# Ethernet.net
KiCad netlist of a schematic drawn in Altium Designer
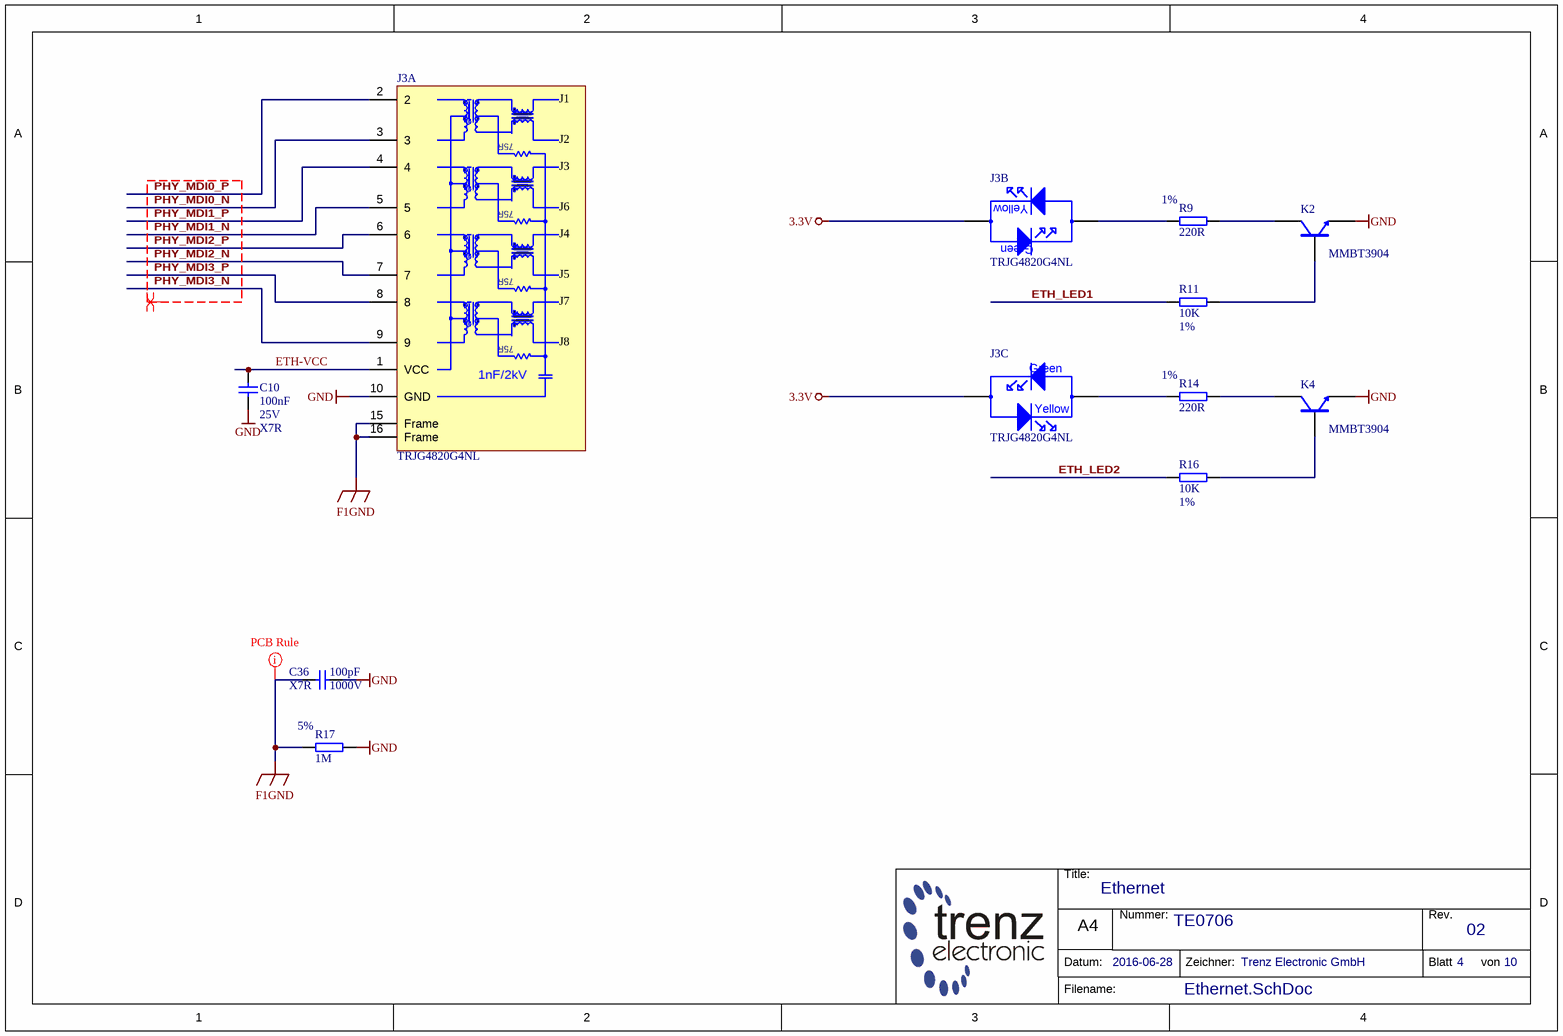
[diagram p0: Ethernet.SchDoc]

(export (version "E")
  (design (tool "Eeschema 10.0.6"))
  (components
    (comp (ref "C10")
      (value "100nF")
      (footprint "CAPC1005X55N")
      (description "KON 100nF 25V X5R SMD")
      (fields (field (name "VOLTAGE") "25V") (field (name "TECHNOLOGY") "X7R"))
      (libsource (lib "TE") (part "CAP-NP"))
    )
    (comp (ref "C36")
      (value "100pF")
      (footprint "CAPC3216X180N")
      (description "KON 100pF 1000V X7R 10%")
      (fields
        (field (name "VOLTAGE") "X7R")
        (field (name "TECHNOLOGY") "1000V")
        (field (name "TOLERANCE") "10%")
      )
      (libsource (lib "TE") (part "CAP-NP"))
    )
    (comp (ref "J3")
      (value "TRJG4820G4NL")
      (footprint "MIC38013-5151T-LF3")
      (description "LAN-Transformer 10/100/1000 BaseT")
      (libsource (lib "TE") (part "WE-RJ45LAN"))
    )
    (comp (ref "K2")
      (value "MMBT3904")
      (footprint "SOT95P280X145-3N")
      (libsource (lib "TE") (part "NPN-SOT23"))
    )
    (comp (ref "K4")
      (value "MMBT3904")
      (footprint "SOT95P280X145-3N")
      (libsource (lib "TE") (part "NPN-SOT23"))
    )
    (comp (ref "R9")
      (value "220R")
      (footprint "RESC1005X40N")
      (description "WID SMD 220R 1% 0,063W")
      (fields (field (name "TOLERANCE") "1%"))
      (libsource (lib "TE") (part "RES"))
    )
    (comp (ref "R11")
      (value "10K")
      (footprint "RESC1005X40N")
      (description "WID SMD 10K 1% 0,063W")
      (fields (field (name "TOLERANCE") "1%"))
      (libsource (lib "TE") (part "RES"))
    )
    (comp (ref "R14")
      (value "220R")
      (footprint "RESC1005X40N")
      (description "WID SMD 220R 1% 0,063W")
      (fields (field (name "TOLERANCE") "1%"))
      (libsource (lib "TE") (part "RES"))
    )
    (comp (ref "R16")
      (value "10K")
      (footprint "RESC1005X40N")
      (description "WID SMD 10K 1% 0,063W")
      (fields (field (name "TOLERANCE") "1%"))
      (libsource (lib "TE") (part "RES"))
    )
    (comp (ref "R17")
      (value "1M")
      (footprint "RESC3216X65N")
      (description "WID SMD 1M 5% 0,25W")
      (fields (field (name "TOLERANCE") "5%"))
      (libsource (lib "TE") (part "RES"))
    )
  )
  (nets
    (net (code "1") (name "/ETH-VCC") (class "Default")
      (node (ref "C10") (pin "2") (pinfunction "2_2") (pintype "passive"))
      (node (ref "J3") (pin "1") (pinfunction "VCC_1") (pintype "power_in"))
    )
    (net (code "2") (name "/ETH_LED1") (class "Default")
      (node (ref "R11") (pin "1") (pinfunction "1_1") (pintype "passive"))
    )
    (net (code "3") (name "/ETH_LED2") (class "Default")
      (node (ref "R16") (pin "1") (pinfunction "1_1") (pintype "passive"))
    )
    (net (code "4") (name "/PHY_MDI0_N") (class "Default")
      (node (ref "J3") (pin "3") (pinfunction "3_3") (pintype "passive"))
    )
    (net (code "5") (name "/PHY_MDI0_P") (class "Default")
      (node (ref "J3") (pin "2") (pinfunction "2_2") (pintype "passive"))
    )
    (net (code "6") (name "/PHY_MDI1_N") (class "Default")
      (node (ref "J3") (pin "5") (pinfunction "5_5") (pintype "passive"))
    )
    (net (code "7") (name "/PHY_MDI1_P") (class "Default")
      (node (ref "J3") (pin "4") (pinfunction "4_4") (pintype "passive"))
    )
    (net (code "8") (name "/PHY_MDI2_N") (class "Default")
      (node (ref "J3") (pin "7") (pinfunction "7_7") (pintype "passive"))
    )
    (net (code "9") (name "/PHY_MDI2_P") (class "Default")
      (node (ref "J3") (pin "6") (pinfunction "6_6") (pintype "passive"))
    )
    (net (code "10") (name "/PHY_MDI3_N") (class "Default")
      (node (ref "J3") (pin "9") (pinfunction "9_9") (pintype "passive"))
    )
    (net (code "11") (name "/PHY_MDI3_P") (class "Default")
      (node (ref "J3") (pin "8") (pinfunction "8_8") (pintype "passive"))
    )
    (net (code "12") (name "3.3V") (class "Default")
      (node (ref "J3") (pin "11") (pinfunction "GREEN_11") (pintype "passive"))
      (node (ref "J3") (pin "14") (pinfunction "YELLOW_14") (pintype "passive"))
    )
    (net (code "13") (name "F1GND") (class "Default")
      (node (ref "C36") (pin "1") (pinfunction "1_1") (pintype "passive"))
      (node (ref "J3") (pin "15") (pinfunction "Frame_15") (pintype "passive"))
      (node (ref "J3") (pin "16") (pinfunction "Frame_16") (pintype "passive"))
      (node (ref "R17") (pin "1") (pinfunction "1_1") (pintype "passive"))
    )
    (net (code "14") (name "GND") (class "Default")
      (node (ref "C10") (pin "1") (pinfunction "1_1") (pintype "passive"))
      (node (ref "C36") (pin "2") (pinfunction "2_2") (pintype "passive"))
      (node (ref "J3") (pin "10") (pinfunction "GND_10") (pintype "power_in"))
      (node (ref "K2") (pin "2") (pinfunction "EMITTER_2") (pintype "passive"))
      (node (ref "K4") (pin "2") (pinfunction "EMITTER_2") (pintype "passive"))
      (node (ref "R17") (pin "2") (pinfunction "2_2") (pintype "passive"))
    )
    (net (code "15") (name "Net-(J3B-YELLOW)") (class "Default")
      (node (ref "J3") (pin "12") (pinfunction "YELLOW_12") (pintype "passive"))
      (node (ref "R9") (pin "1") (pinfunction "1_1") (pintype "passive"))
    )
    (net (code "16") (name "Net-(J3C-GREEN)") (class "Default")
      (node (ref "J3") (pin "13") (pinfunction "GREEN_13") (pintype "passive"))
      (node (ref "R14") (pin "1") (pinfunction "1_1") (pintype "passive"))
    )
    (net (code "17") (name "Net-(K2-BASIS)") (class "Default")
      (node (ref "K2") (pin "1") (pinfunction "BASIS_1") (pintype "passive"))
      (node (ref "R11") (pin "2") (pinfunction "2_2") (pintype "passive"))
    )
    (net (code "18") (name "Net-(K2-COLLECTOR)") (class "Default")
      (node (ref "K2") (pin "3") (pinfunction "COLLECTOR_3") (pintype "passive"))
      (node (ref "R9") (pin "2") (pinfunction "2_2") (pintype "passive"))
    )
    (net (code "19") (name "Net-(K4-BASIS)") (class "Default")
      (node (ref "K4") (pin "1") (pinfunction "BASIS_1") (pintype "passive"))
      (node (ref "R16") (pin "2") (pinfunction "2_2") (pintype "passive"))
    )
    (net (code "20") (name "Net-(K4-COLLECTOR)") (class "Default")
      (node (ref "K4") (pin "3") (pinfunction "COLLECTOR_3") (pintype "passive"))
      (node (ref "R14") (pin "2") (pinfunction "2_2") (pintype "passive"))
    )
  )
)
